# mqtt_doorbell_v1_2.net
KiCad netlist of a schematic drawn in EAGLE
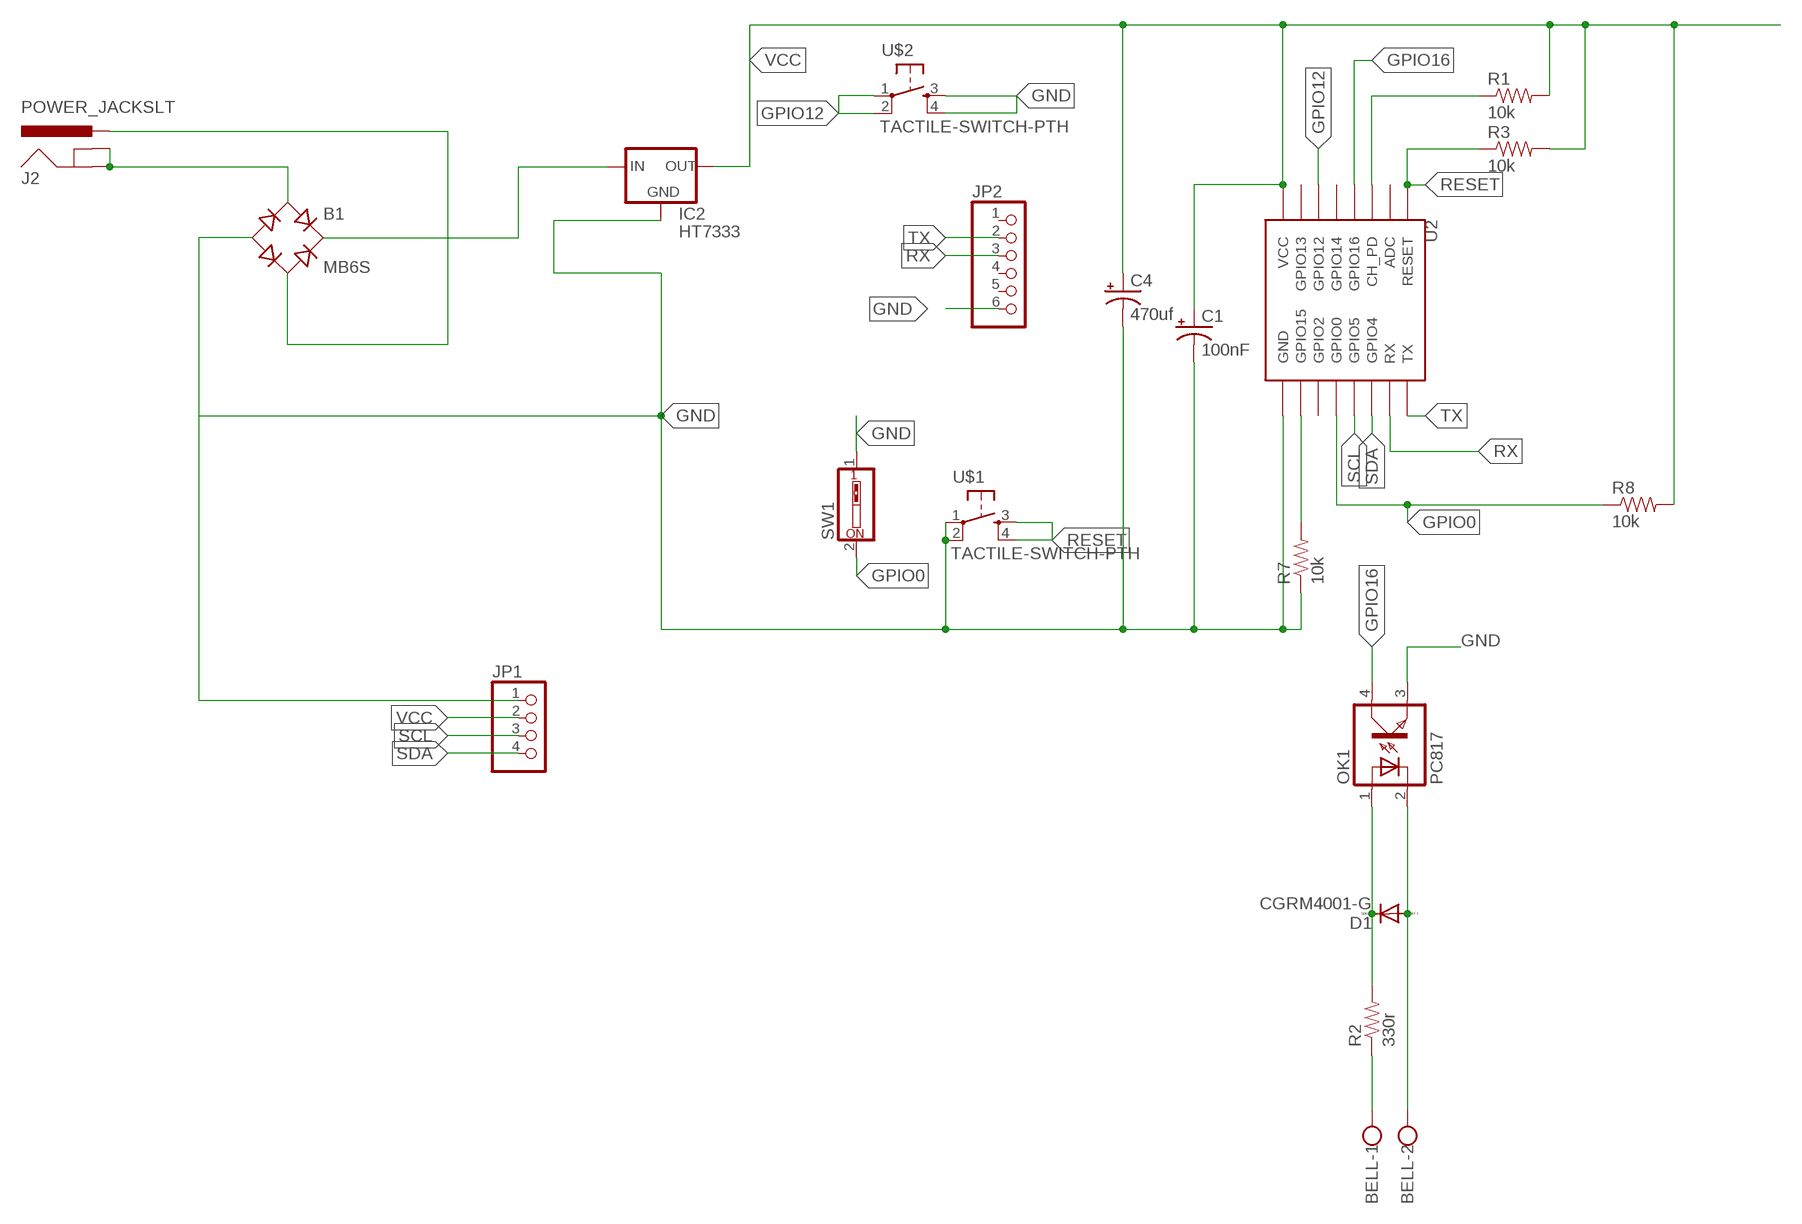
[diagram p0: schematic, sheet 1]

(export (version "E")
  (design (tool "Eeschema 10.0.6"))
  (components
    (comp (ref "B1")
      (value "MB6S")
      (footprint "eagle-import:SOIC-4")
      (libsource (lib "eagle-import") (part "MBS4"))
    )
    (comp (ref "BELL")
      (value "W237-102")
      (footprint "eagle-import:W237-102")
      (fields (field (name "MPN") "237-102"))
      (libsource (lib "eagle-import") (part "W237-102"))
    )
    (comp (ref "C1")
      (value "100nF")
      (footprint "eagle-import:EIA3216")
      (libsource (lib "eagle-import") (part "10UF-16V-10%(TANT)"))
    )
    (comp (ref "C4")
      (value "470uf")
      (footprint "eagle-import:PANASONIC_D")
      (libsource (lib "eagle-import") (part "47UF-50V-20%(ELECT)"))
    )
    (comp (ref "D1")
      (value "CGRM4001-G")
      (footprint "eagle-import:SOD-123_MINI-SMA")
      (libsource (lib "eagle-import") (part "CGRM400-G1"))
    )
    (comp (ref "IC2")
      (value "HT7333")
      (footprint "eagle-import:SOT-89")
      (libsource (lib "eagle-import") (part "HT7333"))
    )
    (comp (ref "J2")
      (value "POWER_JACKSLT")
      (footprint "eagle-import:POWER_JACK_SLOT")
      (libsource (lib "eagle-import") (part "POWER_JACKSLT"))
    )
    (comp (ref "JP1")
      (value "PINHD-1X4")
      (footprint "eagle-import:1X04")
      (libsource (lib "eagle-import") (part "PINHD-1X4"))
    )
    (comp (ref "JP2")
      (value "PINHD-1X6")
      (footprint "eagle-import:1X06")
      (libsource (lib "eagle-import") (part "PINHD-1X6"))
    )
    (comp (ref "OK1")
      (value "PC817")
      (footprint "eagle-import:DIL04")
      (fields (field (name "MPN") "PC817X4J000F"))
      (libsource (lib "eagle-import") (part "PC817"))
    )
    (comp (ref "R1")
      (value "10k")
      (footprint "eagle-import:1206")
      (libsource (lib "eagle-import") (part "RESISTOR1206"))
    )
    (comp (ref "R2")
      (value "330r")
      (footprint "eagle-import:1206")
      (libsource (lib "eagle-import") (part "RESISTOR1206"))
    )
    (comp (ref "R3")
      (value "10k")
      (footprint "eagle-import:1206")
      (libsource (lib "eagle-import") (part "RESISTOR1206"))
    )
    (comp (ref "R7")
      (value "10k")
      (footprint "eagle-import:1206")
      (libsource (lib "eagle-import") (part "RESISTOR1206"))
    )
    (comp (ref "R8")
      (value "10k")
      (footprint "eagle-import:1206")
      (libsource (lib "eagle-import") (part "RESISTOR1206"))
    )
    (comp (ref "SW1")
      (value "SW_DIP-1")
      (footprint "eagle-import:EDG-01")
      (libsource (lib "eagle-import") (part "SW_DIP-1"))
    )
    (comp (ref "U$1")
      (value "TACTILE-SWITCH-PTH")
      (footprint "eagle-import:TAC-SWITCH-PTH")
      (libsource (lib "eagle-import") (part "TACTILE-SWITCH-PTH"))
    )
    (comp (ref "U$2")
      (value "TACTILE-SWITCH-PTH")
      (footprint "eagle-import:TAC-SWITCH-PTH")
      (libsource (lib "eagle-import") (part "TACTILE-SWITCH-PTH"))
    )
    (comp (ref "U2")
      (value "ESP12SMD")
      (footprint "eagle-import:ESP12-SMD")
      (libsource (lib "eagle-import") (part "ESP12SMD"))
    )
  )
  (nets
    (net (code "1") (name "GND") (class "Default")
      (node (ref "B1") (pin "-") (pinfunction "-_-") (pintype "passive"))
      (node (ref "C1") (pin "C") (pinfunction "-_C") (pintype "passive"))
      (node (ref "C4") (pin "-") (pinfunction "-_-") (pintype "passive"))
      (node (ref "IC2") (pin "2") (pinfunction "GND_2") (pintype "input"))
      (node (ref "JP1") (pin "1") (pinfunction "1_1") (pintype "passive"))
      (node (ref "JP2") (pin "6") (pinfunction "6_6") (pintype "passive"))
      (node (ref "OK1") (pin "3") (pinfunction "EMIT_3") (pintype "passive"))
      (node (ref "R7") (pin "1") (pinfunction "1_1") (pintype "passive"))
      (node (ref "SW1") (pin "1") (pinfunction "1_1") (pintype "passive"))
      (node (ref "U$1") (pin "1") (pinfunction "1_1") (pintype "passive"))
      (node (ref "U$1") (pin "2") (pinfunction "2_2") (pintype "passive"))
      (node (ref "U$2") (pin "3") (pinfunction "3_3") (pintype "passive"))
      (node (ref "U$2") (pin "4") (pinfunction "4_4") (pintype "passive"))
      (node (ref "U2") (pin "GND") (pinfunction "GND_GND") (pintype "bidirectional"))
    )
    (net (code "2") (name "GPIO0") (class "Default")
      (node (ref "R8") (pin "1") (pinfunction "1_1") (pintype "passive"))
      (node (ref "SW1") (pin "2") (pinfunction "2_2") (pintype "passive"))
      (node (ref "U2") (pin "GPIO0") (pinfunction "GPIO0_GPIO0") (pintype "bidirectional"))
    )
    (net (code "3") (name "GPIO12") (class "Default")
      (node (ref "U$2") (pin "1") (pinfunction "1_1") (pintype "passive"))
      (node (ref "U$2") (pin "2") (pinfunction "2_2") (pintype "passive"))
      (node (ref "U2") (pin "GPIO12") (pinfunction "GPIO12_GPIO12") (pintype "bidirectional"))
    )
    (net (code "4") (name "GPIO16") (class "Default")
      (node (ref "OK1") (pin "4") (pinfunction "COL_4") (pintype "passive"))
      (node (ref "U2") (pin "GPIO16") (pinfunction "GPIO16_GPIO16") (pintype "bidirectional"))
    )
    (net (code "5") (name "Net-(B1-AC1)") (class "Default")
      (node (ref "B1") (pin "~1") (pinfunction "AC1_~1") (pintype "passive"))
      (node (ref "J2") (pin "GND@1") (pinfunction "GNDBREAK_GND@1") (pintype "bidirectional"))
      (node (ref "J2") (pin "GND@2") (pinfunction "GND_GND@2") (pintype "bidirectional"))
    )
    (net (code "6") (name "Net-(B1-AC2)") (class "Default")
      (node (ref "B1") (pin "~2") (pinfunction "AC2_~2") (pintype "passive"))
      (node (ref "J2") (pin "PWR") (pinfunction "PWR_PWR") (pintype "bidirectional"))
    )
    (net (code "7") (name "Net-(B1-Pad+)") (class "Default")
      (node (ref "B1") (pin "+") (pinfunction "+_+") (pintype "passive"))
      (node (ref "IC2") (pin "3") (pinfunction "IN_3") (pintype "input"))
      (node (ref "IC2") (pin "4") (pinfunction "IN_4") (pintype "input"))
    )
    (net (code "8") (name "Net-(BELLA-KL)") (class "Default")
      (node (ref "BELL") (pin "1") (pinfunction "KL_1") (pintype "passive"))
      (node (ref "R2") (pin "1") (pinfunction "1_1") (pintype "passive"))
    )
    (net (code "9") (name "Net-(BELLB-KL)") (class "Default")
      (node (ref "BELL") (pin "2") (pinfunction "KL_2") (pintype "passive"))
      (node (ref "D1") (pin "A") (pinfunction "A_A") (pintype "passive"))
      (node (ref "OK1") (pin "2") (pinfunction "C_2") (pintype "passive"))
    )
    (net (code "10") (name "Net-(OK1-A)") (class "Default")
      (node (ref "D1") (pin "C") (pinfunction "C_C") (pintype "passive"))
      (node (ref "OK1") (pin "1") (pinfunction "A_1") (pintype "passive"))
      (node (ref "R2") (pin "2") (pinfunction "2_2") (pintype "passive"))
    )
    (net (code "11") (name "Net-(R1-Pad1)") (class "Default")
      (node (ref "R1") (pin "1") (pinfunction "1_1") (pintype "passive"))
      (node (ref "U2") (pin "CH_PD") (pinfunction "CH_PD_CH_PD") (pintype "bidirectional"))
    )
    (net (code "12") (name "Net-(R7-Pad2)") (class "Default")
      (node (ref "R7") (pin "2") (pinfunction "2_2") (pintype "passive"))
      (node (ref "U2") (pin "GPIO15") (pinfunction "GPIO15_GPIO15") (pintype "bidirectional"))
    )
    (net (code "13") (name "RESET") (class "Default")
      (node (ref "R3") (pin "1") (pinfunction "1_1") (pintype "passive"))
      (node (ref "U$1") (pin "3") (pinfunction "3_3") (pintype "passive"))
      (node (ref "U$1") (pin "4") (pinfunction "4_4") (pintype "passive"))
      (node (ref "U2") (pin "RESET") (pinfunction "RESET_RESET") (pintype "bidirectional"))
    )
    (net (code "14") (name "RX") (class "Default")
      (node (ref "JP2") (pin "3") (pinfunction "3_3") (pintype "passive"))
      (node (ref "U2") (pin "RXD0") (pinfunction "RX_RXD0") (pintype "bidirectional"))
    )
    (net (code "15") (name "SCL") (class "Default")
      (node (ref "JP1") (pin "3") (pinfunction "3_3") (pintype "passive"))
      (node (ref "U2") (pin "GPIO5") (pinfunction "GPIO5_GPIO5") (pintype "bidirectional"))
    )
    (net (code "16") (name "SDA") (class "Default")
      (node (ref "JP1") (pin "4") (pinfunction "4_4") (pintype "passive"))
      (node (ref "U2") (pin "GPIO4") (pinfunction "GPIO4_GPIO4") (pintype "bidirectional"))
    )
    (net (code "17") (name "TX") (class "Default")
      (node (ref "JP2") (pin "2") (pinfunction "2_2") (pintype "passive"))
      (node (ref "U2") (pin "TXD0") (pinfunction "TX_TXD0") (pintype "bidirectional"))
    )
    (net (code "18") (name "VCC") (class "Default")
      (node (ref "C1") (pin "A") (pinfunction "+_A") (pintype "passive"))
      (node (ref "C4") (pin "+") (pinfunction "+_+") (pintype "passive"))
      (node (ref "IC2") (pin "1") (pinfunction "OUT_1") (pintype "passive"))
      (node (ref "JP1") (pin "2") (pinfunction "2_2") (pintype "passive"))
      (node (ref "R1") (pin "2") (pinfunction "2_2") (pintype "passive"))
      (node (ref "R3") (pin "2") (pinfunction "2_2") (pintype "passive"))
      (node (ref "R8") (pin "2") (pinfunction "2_2") (pintype "passive"))
      (node (ref "U2") (pin "VCC") (pinfunction "VCC_VCC") (pintype "bidirectional"))
    )
    (net (code "19") (name "unconnected-(JP2-Pad1)") (class "Default")
      (node (ref "JP2") (pin "1") (pinfunction "1_1") (pintype "passive"))
    )
    (net (code "20") (name "unconnected-(JP2-Pad4)") (class "Default")
      (node (ref "JP2") (pin "4") (pinfunction "4_4") (pintype "passive"))
    )
    (net (code "21") (name "unconnected-(JP2-Pad5)") (class "Default")
      (node (ref "JP2") (pin "5") (pinfunction "5_5") (pintype "passive"))
    )
    (net (code "22") (name "unconnected-(U2-PadADC)") (class "Default")
      (node (ref "U2") (pin "ADC") (pinfunction "ADC_ADC") (pintype "bidirectional"))
    )
    (net (code "23") (name "unconnected-(U2-PadGPIO2)") (class "Default")
      (node (ref "U2") (pin "GPIO2") (pinfunction "GPIO2_GPIO2") (pintype "bidirectional"))
    )
    (net (code "24") (name "unconnected-(U2-PadGPIO13)") (class "Default")
      (node (ref "U2") (pin "GPIO13") (pinfunction "GPIO13_GPIO13") (pintype "bidirectional"))
    )
    (net (code "25") (name "unconnected-(U2-PadGPIO14)") (class "Default")
      (node (ref "U2") (pin "GPIO14") (pinfunction "GPIO14_GPIO14") (pintype "bidirectional"))
    )
  )
)
